# ProPrj_ESP32S2-Mini_17__2025-05-19.net
KiCad netlist of a schematic drawn in EasyEDA Pro
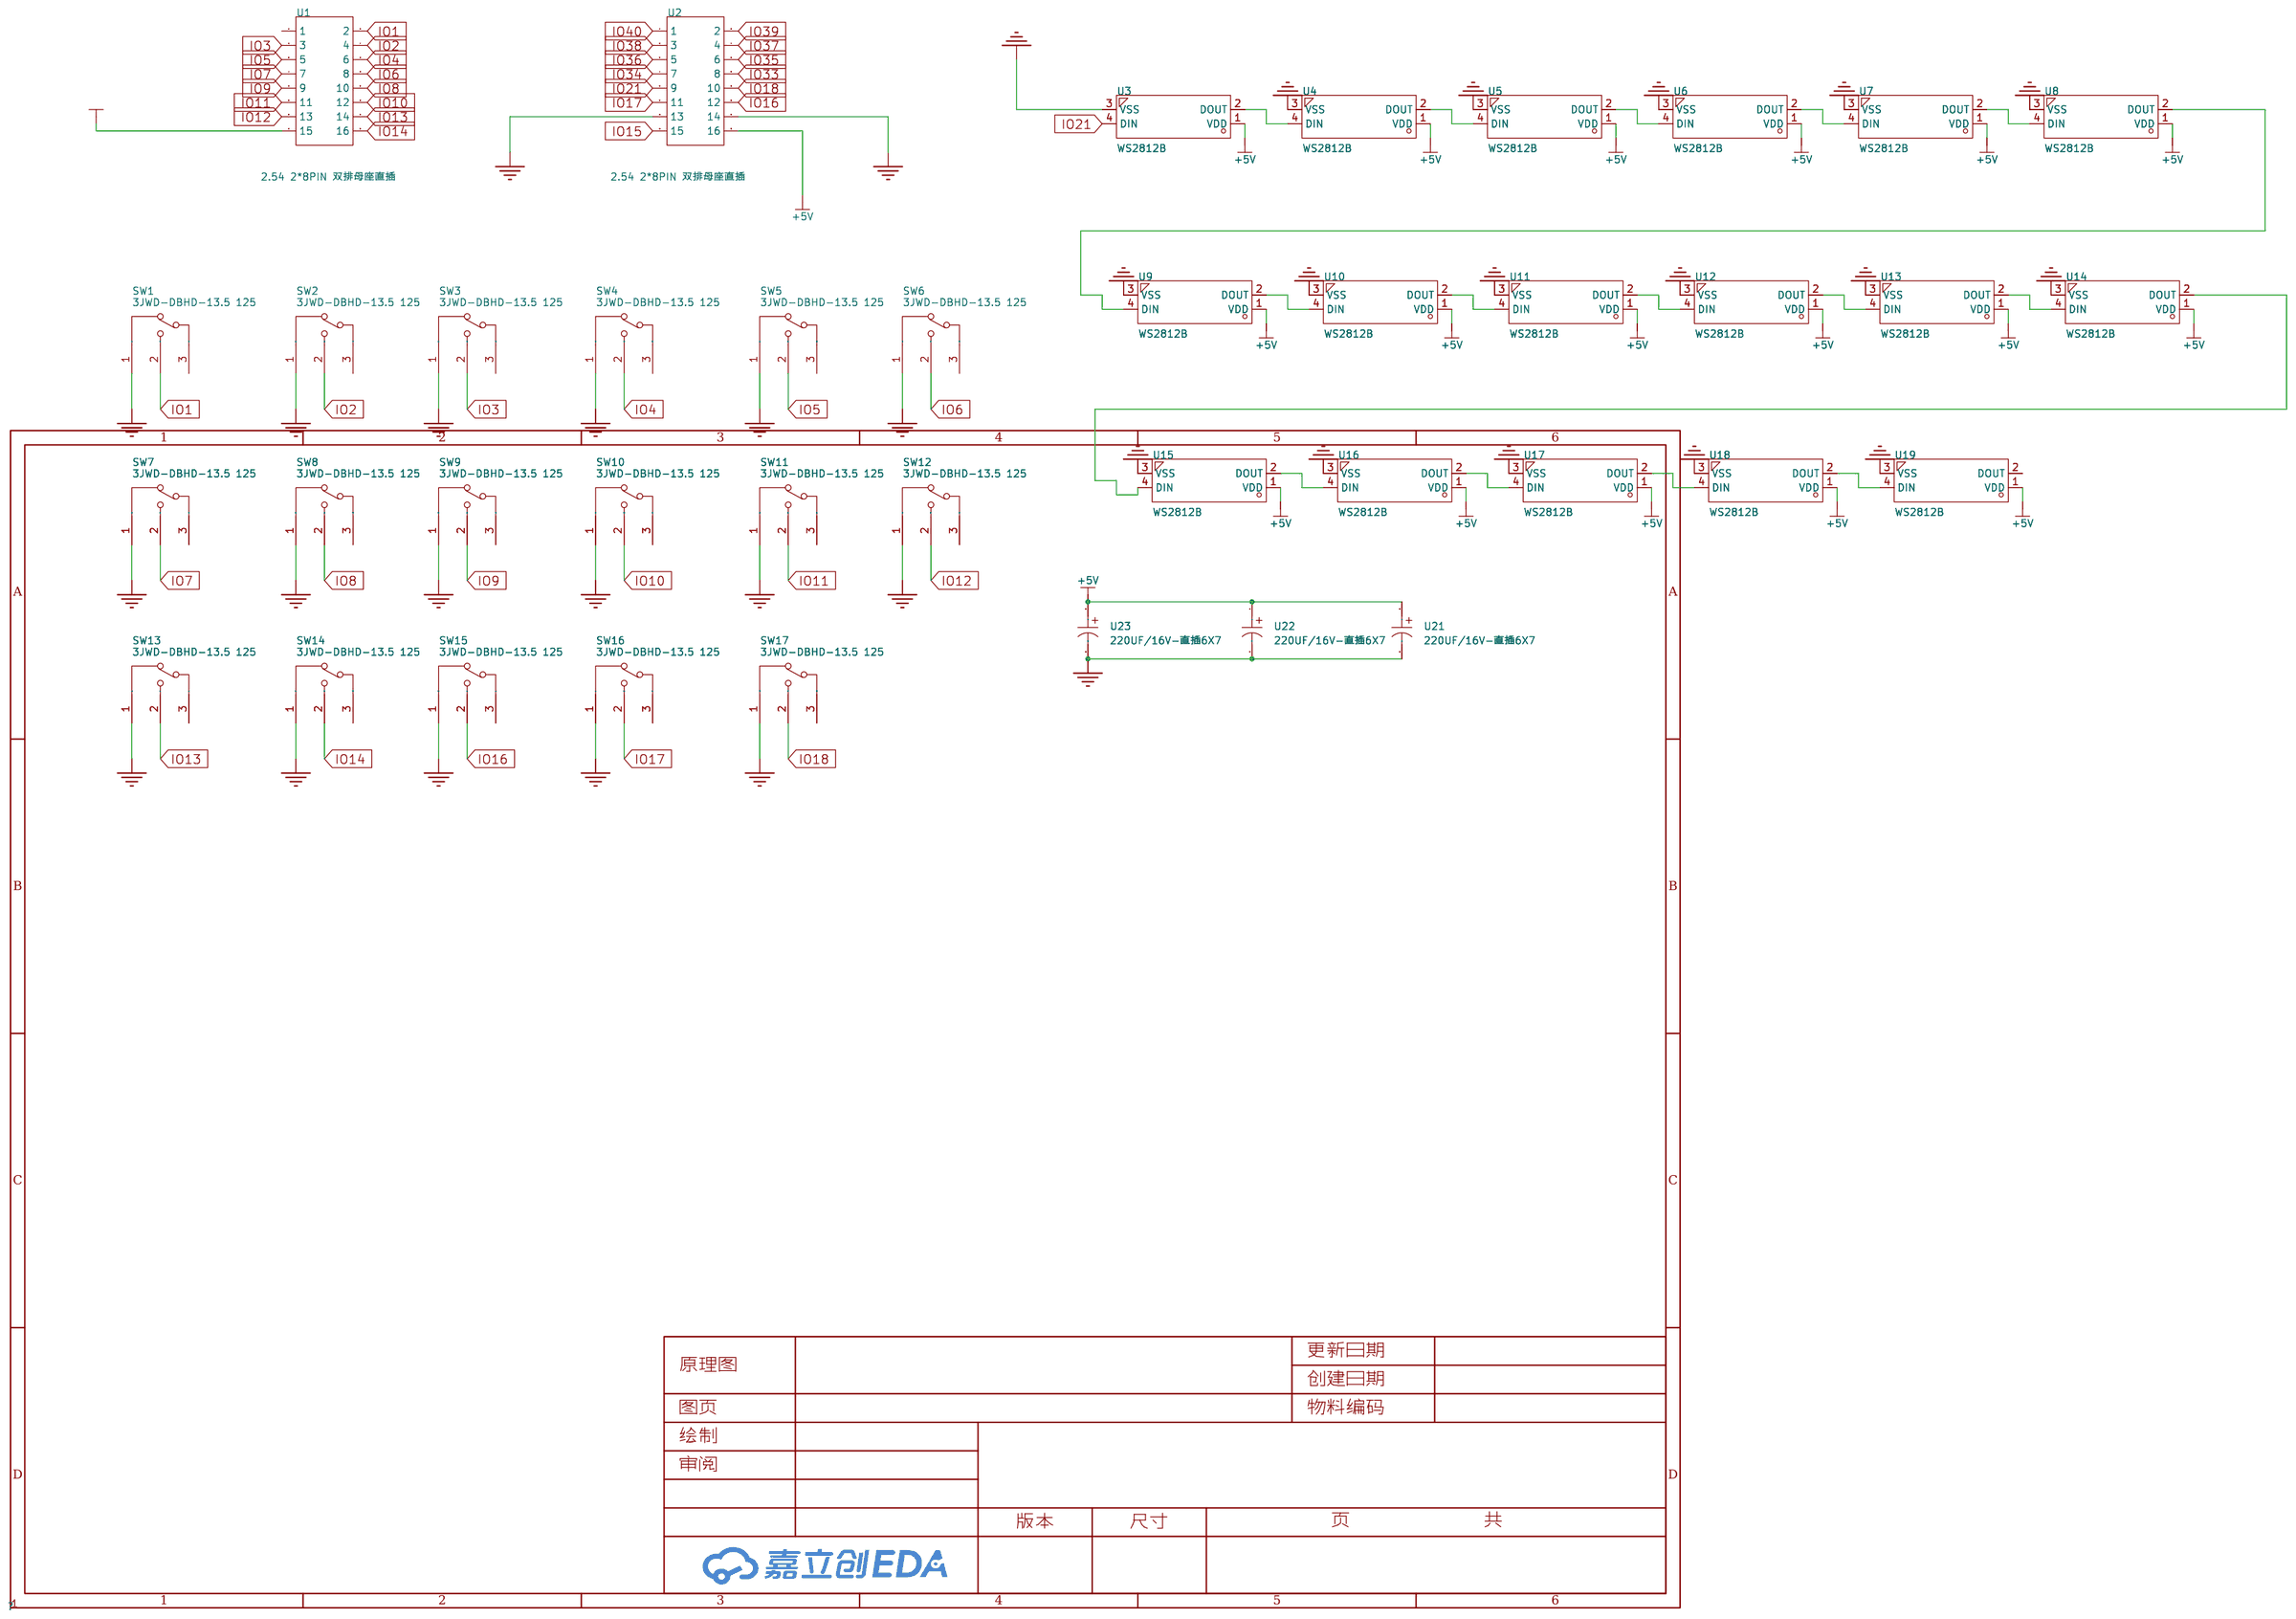
[diagram p0: schematic sheet]

(export (version "E")
  (design (tool "Eeschema 10.0.6"))
  (components
    (comp (ref "SW1")
      (value "3JWD-DBHD-13.5 125")
      (footprint "easyedapro:SW-TH_SHOU-HAN_3JWD-DBHD-13.5")
      (description "鼠标开关 3脚微动开关 红点 柄长13.5mm")
      (fields (field (name "Manufacturer") "SHOU HAN(首韩)"))
      (libsource (lib "easyedapro") (part "3JWD-DBHD-13.5 125"))
    )
    (comp (ref "SW2")
      (value "3JWD-DBHD-13.5 125")
      (footprint "easyedapro:SW-TH_SHOU-HAN_3JWD-DBHD-13.5")
      (description "鼠标开关 3脚微动开关 红点 柄长13.5mm")
      (fields (field (name "Manufacturer") "SHOU HAN(首韩)"))
      (libsource (lib "easyedapro") (part "3JWD-DBHD-13.5 125"))
    )
    (comp (ref "SW3")
      (value "3JWD-DBHD-13.5 125")
      (footprint "easyedapro:SW-TH_SHOU-HAN_3JWD-DBHD-13.5")
      (description "鼠标开关 3脚微动开关 红点 柄长13.5mm")
      (fields (field (name "Manufacturer") "SHOU HAN(首韩)"))
      (libsource (lib "easyedapro") (part "3JWD-DBHD-13.5 125"))
    )
    (comp (ref "SW4")
      (value "3JWD-DBHD-13.5 125")
      (footprint "easyedapro:SW-TH_SHOU-HAN_3JWD-DBHD-13.5")
      (description "鼠标开关 3脚微动开关 红点 柄长13.5mm")
      (fields (field (name "Manufacturer") "SHOU HAN(首韩)"))
      (libsource (lib "easyedapro") (part "3JWD-DBHD-13.5 125"))
    )
    (comp (ref "SW5")
      (value "3JWD-DBHD-13.5 125")
      (footprint "easyedapro:SW-TH_SHOU-HAN_3JWD-DBHD-13.5")
      (description "鼠标开关 3脚微动开关 红点 柄长13.5mm")
      (fields (field (name "Manufacturer") "SHOU HAN(首韩)"))
      (libsource (lib "easyedapro") (part "3JWD-DBHD-13.5 125"))
    )
    (comp (ref "SW6")
      (value "3JWD-DBHD-13.5 125")
      (footprint "easyedapro:SW-TH_SHOU-HAN_3JWD-DBHD-13.5")
      (description "鼠标开关 3脚微动开关 红点 柄长13.5mm")
      (fields (field (name "Manufacturer") "SHOU HAN(首韩)"))
      (libsource (lib "easyedapro") (part "3JWD-DBHD-13.5 125"))
    )
    (comp (ref "SW7")
      (value "3JWD-DBHD-13.5 125")
      (footprint "easyedapro:SW-TH_SHOU-HAN_3JWD-DBHD-13.5")
      (description "鼠标开关 3脚微动开关 红点 柄长13.5mm")
      (fields (field (name "Manufacturer") "SHOU HAN(首韩)"))
      (libsource (lib "easyedapro") (part "3JWD-DBHD-13.5 125"))
    )
    (comp (ref "SW8")
      (value "3JWD-DBHD-13.5 125")
      (footprint "easyedapro:SW-TH_SHOU-HAN_3JWD-DBHD-13.5")
      (description "鼠标开关 3脚微动开关 红点 柄长13.5mm")
      (fields (field (name "Manufacturer") "SHOU HAN(首韩)"))
      (libsource (lib "easyedapro") (part "3JWD-DBHD-13.5 125"))
    )
    (comp (ref "SW9")
      (value "3JWD-DBHD-13.5 125")
      (footprint "easyedapro:SW-TH_SHOU-HAN_3JWD-DBHD-13.5")
      (description "鼠标开关 3脚微动开关 红点 柄长13.5mm")
      (fields (field (name "Manufacturer") "SHOU HAN(首韩)"))
      (libsource (lib "easyedapro") (part "3JWD-DBHD-13.5 125"))
    )
    (comp (ref "SW10")
      (value "3JWD-DBHD-13.5 125")
      (footprint "easyedapro:SW-TH_SHOU-HAN_3JWD-DBHD-13.5")
      (description "鼠标开关 3脚微动开关 红点 柄长13.5mm")
      (fields (field (name "Manufacturer") "SHOU HAN(首韩)"))
      (libsource (lib "easyedapro") (part "3JWD-DBHD-13.5 125"))
    )
    (comp (ref "SW11")
      (value "3JWD-DBHD-13.5 125")
      (footprint "easyedapro:SW-TH_SHOU-HAN_3JWD-DBHD-13.5")
      (description "鼠标开关 3脚微动开关 红点 柄长13.5mm")
      (fields (field (name "Manufacturer") "SHOU HAN(首韩)"))
      (libsource (lib "easyedapro") (part "3JWD-DBHD-13.5 125"))
    )
    (comp (ref "SW12")
      (value "3JWD-DBHD-13.5 125")
      (footprint "easyedapro:SW-TH_SHOU-HAN_3JWD-DBHD-13.5")
      (description "鼠标开关 3脚微动开关 红点 柄长13.5mm")
      (fields (field (name "Manufacturer") "SHOU HAN(首韩)"))
      (libsource (lib "easyedapro") (part "3JWD-DBHD-13.5 125"))
    )
    (comp (ref "SW13")
      (value "3JWD-DBHD-13.5 125")
      (footprint "easyedapro:SW-TH_SHOU-HAN_3JWD-DBHD-13.5")
      (description "鼠标开关 3脚微动开关 红点 柄长13.5mm")
      (fields (field (name "Manufacturer") "SHOU HAN(首韩)"))
      (libsource (lib "easyedapro") (part "3JWD-DBHD-13.5 125"))
    )
    (comp (ref "SW14")
      (value "3JWD-DBHD-13.5 125")
      (footprint "easyedapro:SW-TH_SHOU-HAN_3JWD-DBHD-13.5")
      (description "鼠标开关 3脚微动开关 红点 柄长13.5mm")
      (fields (field (name "Manufacturer") "SHOU HAN(首韩)"))
      (libsource (lib "easyedapro") (part "3JWD-DBHD-13.5 125"))
    )
    (comp (ref "SW15")
      (value "3JWD-DBHD-13.5 125")
      (footprint "easyedapro:SW-TH_SHOU-HAN_3JWD-DBHD-13.5")
      (description "鼠标开关 3脚微动开关 红点 柄长13.5mm")
      (fields (field (name "Manufacturer") "SHOU HAN(首韩)"))
      (libsource (lib "easyedapro") (part "3JWD-DBHD-13.5 125"))
    )
    (comp (ref "SW16")
      (value "3JWD-DBHD-13.5 125")
      (footprint "easyedapro:SW-TH_SHOU-HAN_3JWD-DBHD-13.5")
      (description "鼠标开关 3脚微动开关 红点 柄长13.5mm")
      (fields (field (name "Manufacturer") "SHOU HAN(首韩)"))
      (libsource (lib "easyedapro") (part "3JWD-DBHD-13.5 125"))
    )
    (comp (ref "SW17")
      (value "3JWD-DBHD-13.5 125")
      (footprint "easyedapro:SW-TH_SHOU-HAN_3JWD-DBHD-13.5")
      (description "鼠标开关 3脚微动开关 红点 柄长13.5mm")
      (fields (field (name "Manufacturer") "SHOU HAN(首韩)"))
      (libsource (lib "easyedapro") (part "3JWD-DBHD-13.5 125"))
    )
    (comp (ref "U1")
      (value "2.54 2*8PIN 双排母座直插")
      (footprint "easyedapro:HDR-TH_16P-P2.54-V-F-R2-C8-S2.54-1")
      (libsource (lib "easyedapro") (part "2.54 2*8PIN 双排母座直插"))
    )
    (comp (ref "U2")
      (value "2.54 2*8PIN 双排母座直插")
      (footprint "easyedapro:HDR-TH_16P-P2.54-V-F-R2-C8-S2.54-1")
      (libsource (lib "easyedapro") (part "2.54 2*8PIN 双排母座直插"))
    )
    (comp (ref "U3")
      (value "WS2812B")
      (footprint "easyedapro:LED-SMD_4P-L5.0-W5.0-TL")
      (libsource (lib "easyedapro") (part "WS2812B_C9900106807"))
    )
    (comp (ref "U4")
      (value "WS2812B")
      (footprint "easyedapro:LED-SMD_4P-L5.0-W5.0-TL")
      (libsource (lib "easyedapro") (part "WS2812B_C9900106807"))
    )
    (comp (ref "U5")
      (value "WS2812B")
      (footprint "easyedapro:LED-SMD_4P-L5.0-W5.0-TL")
      (libsource (lib "easyedapro") (part "WS2812B_C9900106807"))
    )
    (comp (ref "U6")
      (value "WS2812B")
      (footprint "easyedapro:LED-SMD_4P-L5.0-W5.0-TL")
      (libsource (lib "easyedapro") (part "WS2812B_C9900106807"))
    )
    (comp (ref "U7")
      (value "WS2812B")
      (footprint "easyedapro:LED-SMD_4P-L5.0-W5.0-TL")
      (libsource (lib "easyedapro") (part "WS2812B_C9900106807"))
    )
    (comp (ref "U8")
      (value "WS2812B")
      (footprint "easyedapro:LED-SMD_4P-L5.0-W5.0-TL")
      (libsource (lib "easyedapro") (part "WS2812B_C9900106807"))
    )
    (comp (ref "U9")
      (value "WS2812B")
      (footprint "easyedapro:LED-SMD_4P-L5.0-W5.0-TL")
      (libsource (lib "easyedapro") (part "WS2812B_C9900106807"))
    )
    (comp (ref "U10")
      (value "WS2812B")
      (footprint "easyedapro:LED-SMD_4P-L5.0-W5.0-TL")
      (libsource (lib "easyedapro") (part "WS2812B_C9900106807"))
    )
    (comp (ref "U11")
      (value "WS2812B")
      (footprint "easyedapro:LED-SMD_4P-L5.0-W5.0-TL")
      (libsource (lib "easyedapro") (part "WS2812B_C9900106807"))
    )
    (comp (ref "U12")
      (value "WS2812B")
      (footprint "easyedapro:LED-SMD_4P-L5.0-W5.0-TL")
      (libsource (lib "easyedapro") (part "WS2812B_C9900106807"))
    )
    (comp (ref "U13")
      (value "WS2812B")
      (footprint "easyedapro:LED-SMD_4P-L5.0-W5.0-TL")
      (libsource (lib "easyedapro") (part "WS2812B_C9900106807"))
    )
    (comp (ref "U14")
      (value "WS2812B")
      (footprint "easyedapro:LED-SMD_4P-L5.0-W5.0-TL")
      (libsource (lib "easyedapro") (part "WS2812B_C9900106807"))
    )
    (comp (ref "U15")
      (value "WS2812B")
      (footprint "easyedapro:LED-SMD_4P-L5.0-W5.0-TL")
      (libsource (lib "easyedapro") (part "WS2812B_C9900106807"))
    )
    (comp (ref "U16")
      (value "WS2812B")
      (footprint "easyedapro:LED-SMD_4P-L5.0-W5.0-TL")
      (libsource (lib "easyedapro") (part "WS2812B_C9900106807"))
    )
    (comp (ref "U17")
      (value "WS2812B")
      (footprint "easyedapro:LED-SMD_4P-L5.0-W5.0-TL")
      (libsource (lib "easyedapro") (part "WS2812B_C9900106807"))
    )
    (comp (ref "U18")
      (value "WS2812B")
      (footprint "easyedapro:LED-SMD_4P-L5.0-W5.0-TL")
      (libsource (lib "easyedapro") (part "WS2812B_C9900106807"))
    )
    (comp (ref "U19")
      (value "WS2812B")
      (footprint "easyedapro:LED-SMD_4P-L5.0-W5.0-TL")
      (libsource (lib "easyedapro") (part "WS2812B_C9900106807"))
    )
    (comp (ref "U21")
      (value "220UF/16V-直插6X7")
      (footprint "easyedapro:CAP-TH_BD6.3-P2.50-D0.5-FD")
      (libsource (lib "easyedapro") (part "220UF/16V-直插6X7"))
    )
    (comp (ref "U22")
      (value "220UF/16V-直插6X7")
      (footprint "easyedapro:CAP-TH_BD6.3-P2.50-D0.5-FD")
      (libsource (lib "easyedapro") (part "220UF/16V-直插6X7"))
    )
    (comp (ref "U23")
      (value "220UF/16V-直插6X7")
      (footprint "easyedapro:CAP-TH_BD6.3-P2.50-D0.5-FD")
      (libsource (lib "easyedapro") (part "220UF/16V-直插6X7"))
    )
  )
  (nets
    (net (code "1") (name "+5V") (class "Default")
      (node (ref "U10") (pin "1") (pinfunction "VDD_1") (pintype "unspecified"))
      (node (ref "U11") (pin "1") (pinfunction "VDD_1") (pintype "unspecified"))
      (node (ref "U12") (pin "1") (pinfunction "VDD_1") (pintype "unspecified"))
      (node (ref "U13") (pin "1") (pinfunction "VDD_1") (pintype "unspecified"))
      (node (ref "U14") (pin "1") (pinfunction "VDD_1") (pintype "unspecified"))
      (node (ref "U15") (pin "1") (pinfunction "VDD_1") (pintype "unspecified"))
      (node (ref "U16") (pin "1") (pinfunction "VDD_1") (pintype "unspecified"))
      (node (ref "U17") (pin "1") (pinfunction "VDD_1") (pintype "unspecified"))
      (node (ref "U18") (pin "1") (pinfunction "VDD_1") (pintype "unspecified"))
      (node (ref "U19") (pin "1") (pinfunction "VDD_1") (pintype "unspecified"))
      (node (ref "U2") (pin "16") (pinfunction "16_16") (pintype "input"))
      (node (ref "U21") (pin "1") (pinfunction "1_1") (pintype "input"))
      (node (ref "U22") (pin "1") (pinfunction "1_1") (pintype "input"))
      (node (ref "U23") (pin "1") (pinfunction "1_1") (pintype "input"))
      (node (ref "U3") (pin "1") (pinfunction "VDD_1") (pintype "unspecified"))
      (node (ref "U4") (pin "1") (pinfunction "VDD_1") (pintype "unspecified"))
      (node (ref "U5") (pin "1") (pinfunction "VDD_1") (pintype "unspecified"))
      (node (ref "U6") (pin "1") (pinfunction "VDD_1") (pintype "unspecified"))
      (node (ref "U7") (pin "1") (pinfunction "VDD_1") (pintype "unspecified"))
      (node (ref "U8") (pin "1") (pinfunction "VDD_1") (pintype "unspecified"))
      (node (ref "U9") (pin "1") (pinfunction "VDD_1") (pintype "unspecified"))
    )
    (net (code "2") (name "GND") (class "Default")
      (node (ref "SW1") (pin "1") (pinfunction "C_1") (pintype "input"))
      (node (ref "SW10") (pin "1") (pinfunction "C_1") (pintype "input"))
      (node (ref "SW11") (pin "1") (pinfunction "C_1") (pintype "input"))
      (node (ref "SW12") (pin "1") (pinfunction "C_1") (pintype "input"))
      (node (ref "SW13") (pin "1") (pinfunction "C_1") (pintype "input"))
      (node (ref "SW14") (pin "1") (pinfunction "C_1") (pintype "input"))
      (node (ref "SW15") (pin "1") (pinfunction "C_1") (pintype "input"))
      (node (ref "SW16") (pin "1") (pinfunction "C_1") (pintype "input"))
      (node (ref "SW17") (pin "1") (pinfunction "C_1") (pintype "input"))
      (node (ref "SW2") (pin "1") (pinfunction "C_1") (pintype "input"))
      (node (ref "SW3") (pin "1") (pinfunction "C_1") (pintype "input"))
      (node (ref "SW4") (pin "1") (pinfunction "C_1") (pintype "input"))
      (node (ref "SW5") (pin "1") (pinfunction "C_1") (pintype "input"))
      (node (ref "SW6") (pin "1") (pinfunction "C_1") (pintype "input"))
      (node (ref "SW7") (pin "1") (pinfunction "C_1") (pintype "input"))
      (node (ref "SW8") (pin "1") (pinfunction "C_1") (pintype "input"))
      (node (ref "SW9") (pin "1") (pinfunction "C_1") (pintype "input"))
      (node (ref "U10") (pin "3") (pinfunction "VSS_3") (pintype "unspecified"))
      (node (ref "U11") (pin "3") (pinfunction "VSS_3") (pintype "unspecified"))
      (node (ref "U12") (pin "3") (pinfunction "VSS_3") (pintype "unspecified"))
      (node (ref "U13") (pin "3") (pinfunction "VSS_3") (pintype "unspecified"))
      (node (ref "U14") (pin "3") (pinfunction "VSS_3") (pintype "unspecified"))
      (node (ref "U15") (pin "3") (pinfunction "VSS_3") (pintype "unspecified"))
      (node (ref "U16") (pin "3") (pinfunction "VSS_3") (pintype "unspecified"))
      (node (ref "U17") (pin "3") (pinfunction "VSS_3") (pintype "unspecified"))
      (node (ref "U18") (pin "3") (pinfunction "VSS_3") (pintype "unspecified"))
      (node (ref "U19") (pin "3") (pinfunction "VSS_3") (pintype "unspecified"))
      (node (ref "U2") (pin "13") (pinfunction "13_13") (pintype "input"))
      (node (ref "U2") (pin "14") (pinfunction "14_14") (pintype "input"))
      (node (ref "U21") (pin "2") (pinfunction "2_2") (pintype "input"))
      (node (ref "U22") (pin "2") (pinfunction "2_2") (pintype "input"))
      (node (ref "U23") (pin "2") (pinfunction "2_2") (pintype "input"))
      (node (ref "U3") (pin "3") (pinfunction "VSS_3") (pintype "unspecified"))
      (node (ref "U4") (pin "3") (pinfunction "VSS_3") (pintype "unspecified"))
      (node (ref "U5") (pin "3") (pinfunction "VSS_3") (pintype "unspecified"))
      (node (ref "U6") (pin "3") (pinfunction "VSS_3") (pintype "unspecified"))
      (node (ref "U7") (pin "3") (pinfunction "VSS_3") (pintype "unspecified"))
      (node (ref "U8") (pin "3") (pinfunction "VSS_3") (pintype "unspecified"))
      (node (ref "U9") (pin "3") (pinfunction "VSS_3") (pintype "unspecified"))
    )
    (net (code "3") (name "IO1") (class "Default")
      (node (ref "SW1") (pin "2") (pinfunction "ON_2") (pintype "input"))
      (node (ref "U1") (pin "2") (pinfunction "2_2") (pintype "input"))
    )
    (net (code "4") (name "IO2") (class "Default")
      (node (ref "SW2") (pin "2") (pinfunction "ON_2") (pintype "input"))
      (node (ref "U1") (pin "4") (pinfunction "4_4") (pintype "input"))
    )
    (net (code "5") (name "IO3") (class "Default")
      (node (ref "SW3") (pin "2") (pinfunction "ON_2") (pintype "input"))
      (node (ref "U1") (pin "3") (pinfunction "3_3") (pintype "input"))
    )
    (net (code "6") (name "IO4") (class "Default")
      (node (ref "SW4") (pin "2") (pinfunction "ON_2") (pintype "input"))
      (node (ref "U1") (pin "6") (pinfunction "6_6") (pintype "input"))
    )
    (net (code "7") (name "IO5") (class "Default")
      (node (ref "SW5") (pin "2") (pinfunction "ON_2") (pintype "input"))
      (node (ref "U1") (pin "5") (pinfunction "5_5") (pintype "input"))
    )
    (net (code "8") (name "IO6") (class "Default")
      (node (ref "SW6") (pin "2") (pinfunction "ON_2") (pintype "input"))
      (node (ref "U1") (pin "8") (pinfunction "8_8") (pintype "input"))
    )
    (net (code "9") (name "IO7") (class "Default")
      (node (ref "SW7") (pin "2") (pinfunction "ON_2") (pintype "input"))
      (node (ref "U1") (pin "7") (pinfunction "7_7") (pintype "input"))
    )
    (net (code "10") (name "IO8") (class "Default")
      (node (ref "SW8") (pin "2") (pinfunction "ON_2") (pintype "input"))
      (node (ref "U1") (pin "10") (pinfunction "10_10") (pintype "input"))
    )
    (net (code "11") (name "IO9") (class "Default")
      (node (ref "SW9") (pin "2") (pinfunction "ON_2") (pintype "input"))
      (node (ref "U1") (pin "9") (pinfunction "9_9") (pintype "input"))
    )
    (net (code "12") (name "IO10") (class "Default")
      (node (ref "SW10") (pin "2") (pinfunction "ON_2") (pintype "input"))
      (node (ref "U1") (pin "12") (pinfunction "12_12") (pintype "input"))
    )
    (net (code "13") (name "IO11") (class "Default")
      (node (ref "SW11") (pin "2") (pinfunction "ON_2") (pintype "input"))
      (node (ref "U1") (pin "11") (pinfunction "11_11") (pintype "input"))
    )
    (net (code "14") (name "IO12") (class "Default")
      (node (ref "SW12") (pin "2") (pinfunction "ON_2") (pintype "input"))
      (node (ref "U1") (pin "13") (pinfunction "13_13") (pintype "input"))
    )
    (net (code "15") (name "IO13") (class "Default")
      (node (ref "SW13") (pin "2") (pinfunction "ON_2") (pintype "input"))
      (node (ref "U1") (pin "14") (pinfunction "14_14") (pintype "input"))
    )
    (net (code "16") (name "IO14") (class "Default")
      (node (ref "SW14") (pin "2") (pinfunction "ON_2") (pintype "input"))
      (node (ref "U1") (pin "16") (pinfunction "16_16") (pintype "input"))
    )
    (net (code "17") (name "IO15") (class "Default")
      (node (ref "U2") (pin "15") (pinfunction "15_15") (pintype "input"))
    )
    (net (code "18") (name "IO16") (class "Default")
      (node (ref "SW15") (pin "2") (pinfunction "ON_2") (pintype "input"))
      (node (ref "U2") (pin "12") (pinfunction "12_12") (pintype "input"))
    )
    (net (code "19") (name "IO17") (class "Default")
      (node (ref "SW16") (pin "2") (pinfunction "ON_2") (pintype "input"))
      (node (ref "U2") (pin "11") (pinfunction "11_11") (pintype "input"))
    )
    (net (code "20") (name "IO18") (class "Default")
      (node (ref "SW17") (pin "2") (pinfunction "ON_2") (pintype "input"))
      (node (ref "U2") (pin "10") (pinfunction "10_10") (pintype "input"))
    )
    (net (code "21") (name "IO21") (class "Default")
      (node (ref "U2") (pin "9") (pinfunction "9_9") (pintype "input"))
      (node (ref "U3") (pin "4") (pinfunction "DIN_4") (pintype "unspecified"))
    )
    (net (code "22") (name "IO33") (class "Default")
      (node (ref "U2") (pin "8") (pinfunction "8_8") (pintype "input"))
    )
    (net (code "23") (name "IO34") (class "Default")
      (node (ref "U2") (pin "7") (pinfunction "7_7") (pintype "input"))
    )
    (net (code "24") (name "IO35") (class "Default")
      (node (ref "U2") (pin "6") (pinfunction "6_6") (pintype "input"))
    )
    (net (code "25") (name "IO36") (class "Default")
      (node (ref "U2") (pin "5") (pinfunction "5_5") (pintype "input"))
    )
    (net (code "26") (name "IO37") (class "Default")
      (node (ref "U2") (pin "4") (pinfunction "4_4") (pintype "input"))
    )
    (net (code "27") (name "IO38") (class "Default")
      (node (ref "U2") (pin "3") (pinfunction "3_3") (pintype "input"))
    )
    (net (code "28") (name "IO39") (class "Default")
      (node (ref "U2") (pin "2") (pinfunction "2_2") (pintype "input"))
    )
    (net (code "29") (name "IO40") (class "Default")
      (node (ref "U2") (pin "1") (pinfunction "1_1") (pintype "input"))
    )
    (net (code "30") (name "Net-(U3-DOUT)") (class "Default")
      (node (ref "U3") (pin "2") (pinfunction "DOUT_2") (pintype "unspecified"))
      (node (ref "U4") (pin "4") (pinfunction "DIN_4") (pintype "unspecified"))
    )
    (net (code "31") (name "Net-(U4-DOUT)") (class "Default")
      (node (ref "U4") (pin "2") (pinfunction "DOUT_2") (pintype "unspecified"))
      (node (ref "U5") (pin "4") (pinfunction "DIN_4") (pintype "unspecified"))
    )
    (net (code "32") (name "Net-(U5-DOUT)") (class "Default")
      (node (ref "U5") (pin "2") (pinfunction "DOUT_2") (pintype "unspecified"))
      (node (ref "U6") (pin "4") (pinfunction "DIN_4") (pintype "unspecified"))
    )
    (net (code "33") (name "Net-(U6-DOUT)") (class "Default")
      (node (ref "U6") (pin "2") (pinfunction "DOUT_2") (pintype "unspecified"))
      (node (ref "U7") (pin "4") (pinfunction "DIN_4") (pintype "unspecified"))
    )
    (net (code "34") (name "Net-(U7-DOUT)") (class "Default")
      (node (ref "U7") (pin "2") (pinfunction "DOUT_2") (pintype "unspecified"))
      (node (ref "U8") (pin "4") (pinfunction "DIN_4") (pintype "unspecified"))
    )
    (net (code "35") (name "Net-(U8-DOUT)") (class "Default")
      (node (ref "U8") (pin "2") (pinfunction "DOUT_2") (pintype "unspecified"))
      (node (ref "U9") (pin "4") (pinfunction "DIN_4") (pintype "unspecified"))
    )
    (net (code "36") (name "Net-(U10-DIN)") (class "Default")
      (node (ref "U10") (pin "4") (pinfunction "DIN_4") (pintype "unspecified"))
      (node (ref "U9") (pin "2") (pinfunction "DOUT_2") (pintype "unspecified"))
    )
    (net (code "37") (name "Net-(U10-DOUT)") (class "Default")
      (node (ref "U10") (pin "2") (pinfunction "DOUT_2") (pintype "unspecified"))
      (node (ref "U11") (pin "4") (pinfunction "DIN_4") (pintype "unspecified"))
    )
    (net (code "38") (name "Net-(U11-DOUT)") (class "Default")
      (node (ref "U11") (pin "2") (pinfunction "DOUT_2") (pintype "unspecified"))
      (node (ref "U12") (pin "4") (pinfunction "DIN_4") (pintype "unspecified"))
    )
    (net (code "39") (name "Net-(U12-DOUT)") (class "Default")
      (node (ref "U12") (pin "2") (pinfunction "DOUT_2") (pintype "unspecified"))
      (node (ref "U13") (pin "4") (pinfunction "DIN_4") (pintype "unspecified"))
    )
    (net (code "40") (name "Net-(U13-DOUT)") (class "Default")
      (node (ref "U13") (pin "2") (pinfunction "DOUT_2") (pintype "unspecified"))
      (node (ref "U14") (pin "4") (pinfunction "DIN_4") (pintype "unspecified"))
    )
    (net (code "41") (name "Net-(U14-DOUT)") (class "Default")
      (node (ref "U14") (pin "2") (pinfunction "DOUT_2") (pintype "unspecified"))
      (node (ref "U15") (pin "4") (pinfunction "DIN_4") (pintype "unspecified"))
    )
    (net (code "42") (name "Net-(U15-DOUT)") (class "Default")
      (node (ref "U15") (pin "2") (pinfunction "DOUT_2") (pintype "unspecified"))
      (node (ref "U16") (pin "4") (pinfunction "DIN_4") (pintype "unspecified"))
    )
    (net (code "43") (name "Net-(U16-DOUT)") (class "Default")
      (node (ref "U16") (pin "2") (pinfunction "DOUT_2") (pintype "unspecified"))
      (node (ref "U17") (pin "4") (pinfunction "DIN_4") (pintype "unspecified"))
    )
    (net (code "44") (name "Net-(U17-DOUT)") (class "Default")
      (node (ref "U17") (pin "2") (pinfunction "DOUT_2") (pintype "unspecified"))
      (node (ref "U18") (pin "4") (pinfunction "DIN_4") (pintype "unspecified"))
    )
    (net (code "45") (name "Net-(U18-DOUT)") (class "Default")
      (node (ref "U18") (pin "2") (pinfunction "DOUT_2") (pintype "unspecified"))
      (node (ref "U19") (pin "4") (pinfunction "DIN_4") (pintype "unspecified"))
    )
    (net (code "46") (name "VCC3v3") (class "Default")
      (node (ref "U1") (pin "15") (pinfunction "15_15") (pintype "input"))
    )
    (net (code "47") (name "unconnected-(SW1-NC-Pad3)") (class "Default")
      (node (ref "SW1") (pin "3") (pinfunction "NC_3") (pintype "input"))
    )
    (net (code "48") (name "unconnected-(SW2-NC-Pad3)") (class "Default")
      (node (ref "SW2") (pin "3") (pinfunction "NC_3") (pintype "input"))
    )
    (net (code "49") (name "unconnected-(SW3-NC-Pad3)") (class "Default")
      (node (ref "SW3") (pin "3") (pinfunction "NC_3") (pintype "input"))
    )
    (net (code "50") (name "unconnected-(SW4-NC-Pad3)") (class "Default")
      (node (ref "SW4") (pin "3") (pinfunction "NC_3") (pintype "input"))
    )
    (net (code "51") (name "unconnected-(SW5-NC-Pad3)") (class "Default")
      (node (ref "SW5") (pin "3") (pinfunction "NC_3") (pintype "input"))
    )
    (net (code "52") (name "unconnected-(SW6-NC-Pad3)") (class "Default")
      (node (ref "SW6") (pin "3") (pinfunction "NC_3") (pintype "input"))
    )
    (net (code "53") (name "unconnected-(SW7-NC-Pad3)") (class "Default")
      (node (ref "SW7") (pin "3") (pinfunction "NC_3") (pintype "input"))
    )
    (net (code "54") (name "unconnected-(SW8-NC-Pad3)") (class "Default")
      (node (ref "SW8") (pin "3") (pinfunction "NC_3") (pintype "input"))
    )
    (net (code "55") (name "unconnected-(SW9-NC-Pad3)") (class "Default")
      (node (ref "SW9") (pin "3") (pinfunction "NC_3") (pintype "input"))
    )
    (net (code "56") (name "unconnected-(SW10-NC-Pad3)") (class "Default")
      (node (ref "SW10") (pin "3") (pinfunction "NC_3") (pintype "input"))
    )
    (net (code "57") (name "unconnected-(SW11-NC-Pad3)") (class "Default")
      (node (ref "SW11") (pin "3") (pinfunction "NC_3") (pintype "input"))
    )
    (net (code "58") (name "unconnected-(SW12-NC-Pad3)") (class "Default")
      (node (ref "SW12") (pin "3") (pinfunction "NC_3") (pintype "input"))
    )
    (net (code "59") (name "unconnected-(SW13-NC-Pad3)") (class "Default")
      (node (ref "SW13") (pin "3") (pinfunction "NC_3") (pintype "input"))
    )
    (net (code "60") (name "unconnected-(SW14-NC-Pad3)") (class "Default")
      (node (ref "SW14") (pin "3") (pinfunction "NC_3") (pintype "input"))
    )
    (net (code "61") (name "unconnected-(SW15-NC-Pad3)") (class "Default")
      (node (ref "SW15") (pin "3") (pinfunction "NC_3") (pintype "input"))
    )
    (net (code "62") (name "unconnected-(SW16-NC-Pad3)") (class "Default")
      (node (ref "SW16") (pin "3") (pinfunction "NC_3") (pintype "input"))
    )
    (net (code "63") (name "unconnected-(SW17-NC-Pad3)") (class "Default")
      (node (ref "SW17") (pin "3") (pinfunction "NC_3") (pintype "input"))
    )
    (net (code "64") (name "unconnected-(U1-Pad1)") (class "Default")
      (node (ref "U1") (pin "1") (pinfunction "1_1") (pintype "input"))
    )
    (net (code "65") (name "unconnected-(U19-DOUT-Pad2)") (class "Default")
      (node (ref "U19") (pin "2") (pinfunction "DOUT_2") (pintype "unspecified"))
    )
  )
)
